# Power_Supply.net
KiCad netlist of a schematic drawn in Altium Designer
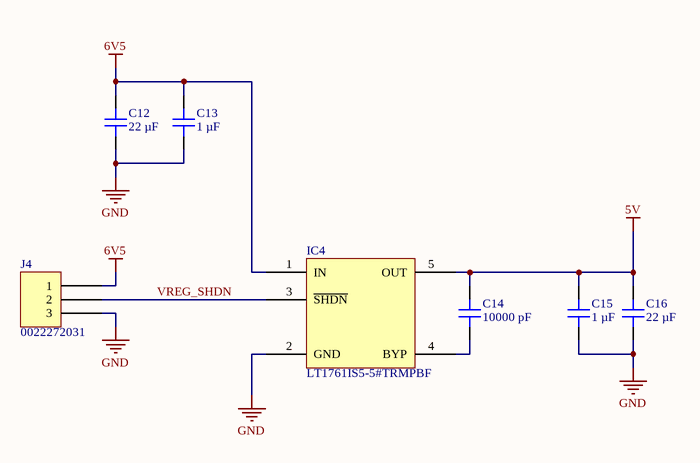
[diagram p0: Power Supply.SchDoc]

(export (version "E")
  (design (tool "Eeschema 10.0.6"))
  (components
    (comp (ref "C12")
      (value "22 µF")
      (footprint "CAP 0603_1608")
      (description "CAP CER 22UF 10V X5R 0603")
      (fields
        (field (name "PART NUMBER") "CL10A226MP8NUNE")
        (field (name "MANUFACTURER") "Samsung Electro-Mechanics")
      )
      (libsource (lib "altiumlibrary.com") (part "Capacitor"))
    )
    (comp (ref "C13")
      (value "1 µF")
      (footprint "CAP 0603_1608")
      (description "CAP CER 1UF 25V X7R 0603")
      (fields
        (field (name "PART NUMBER") "GCM188R71E105KA64D")
        (field (name "MANUFACTURER") "Murata Electronics")
      )
      (libsource (lib "altiumlibrary.com") (part "Capacitor"))
    )
    (comp (ref "C14")
      (value "10000 pF")
      (footprint "CAP 0402_1005")
      (description "CAP CER 10000PF 50V X7R 0402")
      (fields
        (field (name "PART NUMBER") "GCM155R71H103KA55D")
        (field (name "MANUFACTURER") "Murata Electronics")
      )
      (libsource (lib "altiumlibrary.com") (part "Capacitor"))
    )
    (comp (ref "C15")
      (value "1 µF")
      (footprint "CAP 0603_1608")
      (description "CAP CER 1UF 25V X7R 0603")
      (fields
        (field (name "PART NUMBER") "GCM188R71E105KA64D")
        (field (name "MANUFACTURER") "Murata Electronics")
      )
      (libsource (lib "altiumlibrary.com") (part "Capacitor"))
    )
    (comp (ref "C16")
      (value "22 µF")
      (footprint "CAP 0603_1608")
      (description "CAP CER 22UF 10V X5R 0603")
      (fields
        (field (name "PART NUMBER") "CL10A226MP8NUNE")
        (field (name "MANUFACTURER") "Samsung Electro-Mechanics")
      )
      (libsource (lib "altiumlibrary.com") (part "Capacitor"))
    )
    (comp (ref "IC4")
      (value "LT1761IS5-5#TRMPBF")
      (footprint "AD SOT-23-5 S5  05-08-1635")
      (description "IC REG LINEAR 5V 100MA TSOT23-5")
      (fields (field (name "MANUFACTURER") "Analog Devices Inc."))
      (libsource (lib "altiumlibrary.com") (part "AD LT1761-X S5"))
    )
    (comp (ref "J4")
      (value "0022272031")
      (footprint "MOLEX KK 0022272031")
      (description "CONN HEADER VERT 3POS 2.54MM")
      (fields (field (name "MANUFACTURER") "Molex"))
      (libsource (lib "altiumlibrary.com") (part "3 Pin"))
    )
  )
  (nets
    (net (code "1") (name "/VREG_SHDN") (class "Default")
      (node (ref "IC4") (pin "3") (pinfunction "~{SHDN}_3") (pintype "passive"))
      (node (ref "J4") (pin "2") (pinfunction "2_2") (pintype "passive"))
    )
    (net (code "2") (name "5V") (class "Default")
      (node (ref "C14") (pin "1") (pinfunction "1_1") (pintype "passive"))
      (node (ref "C15") (pin "2") (pinfunction "2_2") (pintype "passive"))
      (node (ref "C16") (pin "2") (pinfunction "2_2") (pintype "passive"))
      (node (ref "IC4") (pin "5") (pinfunction "OUT_5") (pintype "passive"))
    )
    (net (code "3") (name "6V5") (class "Default")
      (node (ref "C12") (pin "2") (pinfunction "2_2") (pintype "passive"))
      (node (ref "C13") (pin "2") (pinfunction "2_2") (pintype "passive"))
      (node (ref "IC4") (pin "1") (pinfunction "IN_1") (pintype "passive"))
      (node (ref "J4") (pin "1") (pinfunction "1_1") (pintype "passive"))
    )
    (net (code "4") (name "GND") (class "Default")
      (node (ref "C12") (pin "1") (pinfunction "1_1") (pintype "passive"))
      (node (ref "C13") (pin "1") (pinfunction "1_1") (pintype "passive"))
      (node (ref "C15") (pin "1") (pinfunction "1_1") (pintype "passive"))
      (node (ref "C16") (pin "1") (pinfunction "1_1") (pintype "passive"))
      (node (ref "IC4") (pin "2") (pinfunction "GND_2") (pintype "passive"))
      (node (ref "J4") (pin "3") (pinfunction "3_3") (pintype "passive"))
    )
    (net (code "5") (name "Net-(IC4-BYP)") (class "Default")
      (node (ref "C14") (pin "2") (pinfunction "2_2") (pintype "passive"))
      (node (ref "IC4") (pin "4") (pinfunction "BYP_4") (pintype "passive"))
    )
  )
)
